# lpc11c14_33.net
KiCad netlist of a schematic drawn in Altium Designer
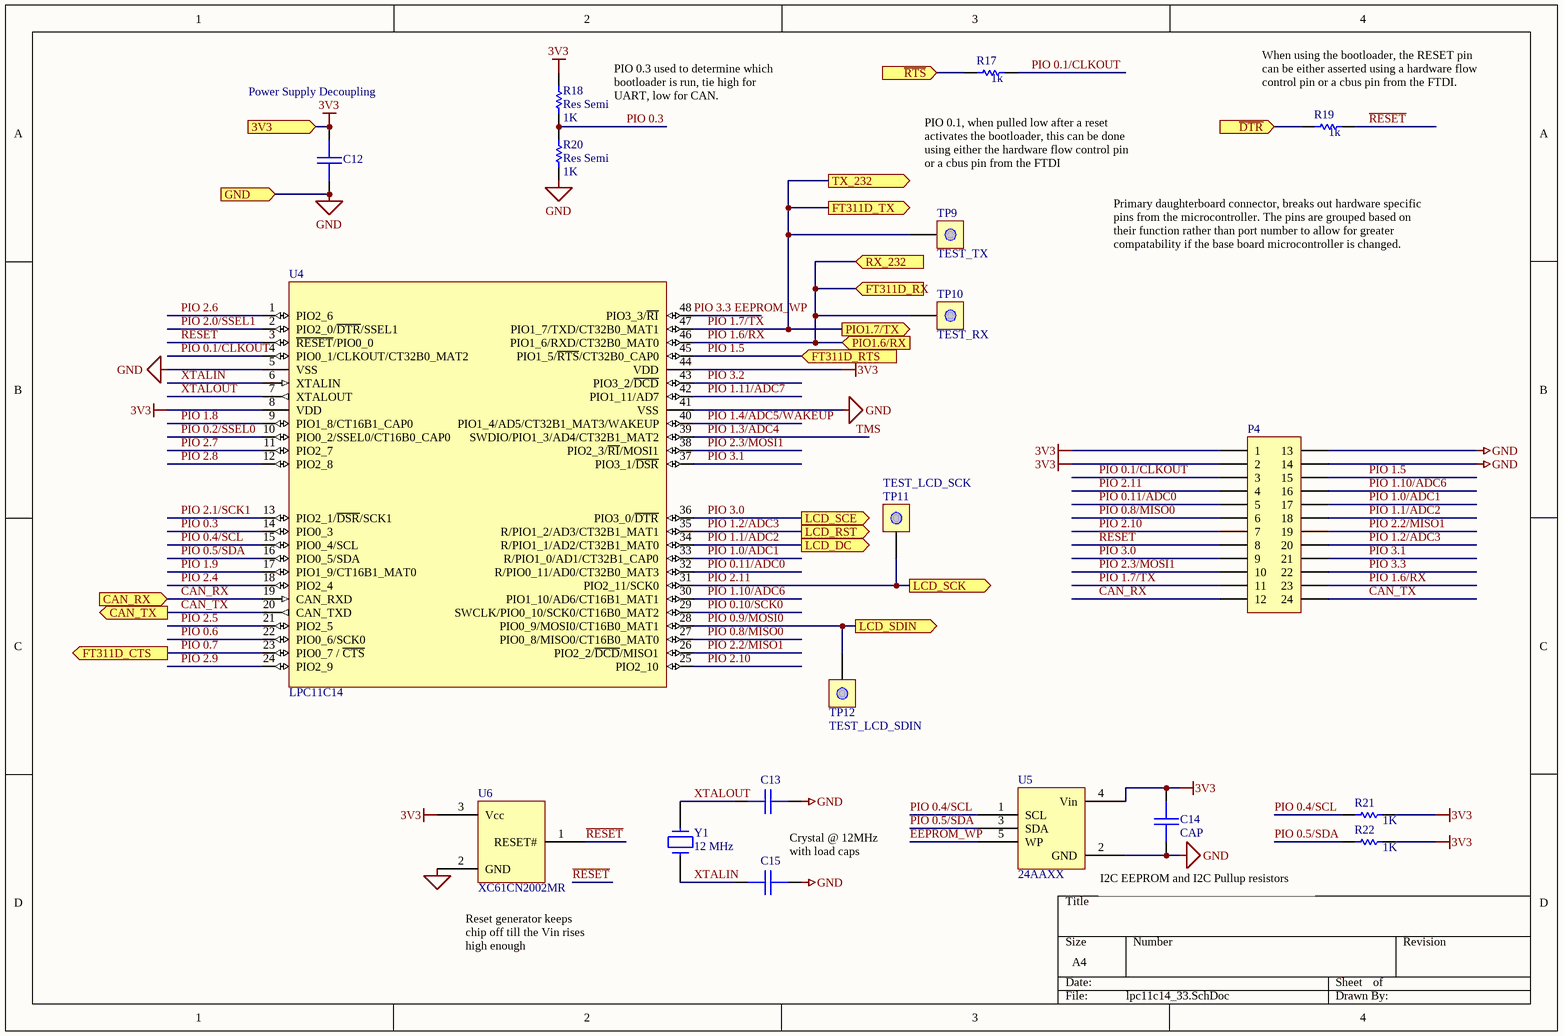
[diagram p0: lpc11c14_33.SchDoc]

(export (version "E")
  (design (tool "Eeschema 10.0.6"))
  (components
    (comp (ref "C12")
      (value "CAP")
      (footprint "0603")
      (description "Capacitor")
      (libsource (lib "RCLDQ") (part "CAP"))
    )
    (comp (ref "C13")
      (value "CAP")
      (footprint "0603")
      (description "Capacitor")
      (libsource (lib "RCLDQ") (part "CAP"))
    )
    (comp (ref "C14")
      (value "CAP")
      (footprint "0603")
      (description "Capacitor")
      (libsource (lib "RCLDQ") (part "CAP"))
    )
    (comp (ref "C15")
      (value "CAP")
      (footprint "0603")
      (description "Capacitor")
      (libsource (lib "RCLDQ") (part "CAP"))
    )
    (comp (ref "P4")
      (value "Header 12X2A")
      (footprint "HDR2X12_CEN")
      (description "Header, 12-Pin, Dual row")
      (fields (field (name "PUBLISHER") "Altium Limited"))
      (libsource (lib "Miscellaneous Connectors") (part "Header 12X2A"))
    )
    (comp (ref "R17")
      (value "1k")
      (footprint "0603")
      (description "Semiconductor Resistor")
      (fields (field (name "Comment") "Res Semi") (field (name "PUBLISHER") "Altium Limited"))
      (libsource (lib "Miscellaneous Devices") (part "Res Semi"))
    )
    (comp (ref "R18")
      (value "Res Semi")
      (footprint "0603")
      (description "Semiconductor Resistor")
      (fields (field (name "ALTIUM_VALUE") "1K") (field (name "PUBLISHER") "Altium Limited"))
      (libsource (lib "Miscellaneous Devices") (part "Res Semi"))
    )
    (comp (ref "R19")
      (value "1k")
      (footprint "0603")
      (description "Semiconductor Resistor")
      (fields (field (name "Comment") "Res Semi") (field (name "PUBLISHER") "Altium Limited"))
      (libsource (lib "Miscellaneous Devices") (part "Res Semi"))
    )
    (comp (ref "R20")
      (value "Res Semi")
      (footprint "0603")
      (description "Semiconductor Resistor")
      (fields (field (name "ALTIUM_VALUE") "1K") (field (name "PUBLISHER") "Altium Limited"))
      (libsource (lib "Miscellaneous Devices") (part "Res Semi"))
    )
    (comp (ref "R21")
      (value "1K")
      (footprint "0603")
      (description "Semiconductor Resistor")
      (fields (field (name "Comment") "Res Semi") (field (name "PUBLISHER") "Altium Limited"))
      (libsource (lib "Miscellaneous Devices") (part "Res Semi"))
    )
    (comp (ref "R22")
      (value "1K")
      (footprint "0603")
      (description "Semiconductor Resistor")
      (fields (field (name "Comment") "Res Semi") (field (name "PUBLISHER") "Altium Limited"))
      (libsource (lib "Miscellaneous Devices") (part "Res Semi"))
    )
    (comp (ref "TP9")
      (value "TEST_TX")
      (footprint "TESTPOINT")
      (description "TEST POINT")
      (libsource (lib "Miscellaneous") (part "TEST"))
    )
    (comp (ref "TP10")
      (value "TEST_RX")
      (footprint "TESTPOINT")
      (description "TEST POINT")
      (libsource (lib "Miscellaneous") (part "TEST"))
    )
    (comp (ref "TP11")
      (value "TEST_LCD_SCK")
      (footprint "TESTPOINT")
      (description "TEST POINT")
      (libsource (lib "") (part "TEST_1"))
    )
    (comp (ref "TP12")
      (value "TEST_LCD_SDIN")
      (footprint "TESTPOINT")
      (description "TEST POINT")
      (libsource (lib "") (part "TEST_2"))
    )
    (comp (ref "U4")
      (value "LPC11C14")
      (footprint "QFP48")
      (description "NXP LPC11C14 Microcontroller")
      (libsource (lib "LPC") (part "LPC11C14_Full"))
    )
    (comp (ref "U5")
      (value "24AAXX")
      (footprint "SOT23-5")
      (description "I2C EEPROM for SOT23-5 package")
      (libsource (lib "MiscellaneousIC") (part "24AAXX"))
    )
    (comp (ref "U6")
      (value "XC61CN2002MR")
      (footprint "SOT23-3")
      (description "SOT23 reset generator")
      (libsource (lib "*") (part "XC61F"))
    )
    (comp (ref "Y1")
      (value "12 MHz")
      (footprint "HC49/4H")
      (description "Crystal")
      (libsource (lib "*") (part "CRYSTAL"))
    )
  )
  (nets
    (net (code "1") (name "/CAN_RX") (class "Default")
      (node (ref "P4") (pin "12") (pinfunction "12_12") (pintype "passive"))
      (node (ref "U4") (pin "19") (pinfunction "CAN_RXD_19") (pintype "input"))
    )
    (net (code "2") (name "/CAN_TX") (class "Default")
      (node (ref "P4") (pin "24") (pinfunction "24_24") (pintype "passive"))
      (node (ref "U4") (pin "20") (pinfunction "CAN_TXD_20") (pintype "output"))
    )
    (net (code "3") (name "/EEPROM_WP") (class "Default")
      (node (ref "P4") (pin "22") (pinfunction "22_22") (pintype "passive"))
      (node (ref "U4") (pin "48") (pinfunction "PIO3_3/~{RI}_48") (pintype "bidirectional"))
      (node (ref "U5") (pin "5") (pinfunction "WP_5") (pintype "passive"))
    )
    (net (code "4") (name "/PIO 0.1{slash}CLKOUT") (class "Default")
      (node (ref "P4") (pin "3") (pinfunction "3_3") (pintype "passive"))
      (node (ref "R17") (pin "2") (pinfunction "2_2") (pintype "passive"))
      (node (ref "U4") (pin "4") (pinfunction "PIO0_1/CLKOUT/CT32B0_MAT2_4") (pintype "bidirectional"))
    )
    (net (code "5") (name "/PIO 0.2{slash}SSEL0") (class "Default")
      (node (ref "U4") (pin "10") (pinfunction "PIO0_2/SSEL0/CT16B0_CAP0_10") (pintype "bidirectional"))
    )
    (net (code "6") (name "/PIO 0.3") (class "Default")
      (node (ref "R18") (pin "1") (pinfunction "1_1") (pintype "passive"))
      (node (ref "R20") (pin "2") (pinfunction "2_2") (pintype "passive"))
      (node (ref "U4") (pin "14") (pinfunction "PIO0_3_14") (pintype "bidirectional"))
    )
    (net (code "7") (name "/PIO 0.4{slash}SCL") (class "Default")
      (node (ref "R21") (pin "1") (pinfunction "1_1") (pintype "passive"))
      (node (ref "U4") (pin "15") (pinfunction "PIO0_4/SCL_15") (pintype "bidirectional"))
      (node (ref "U5") (pin "1") (pinfunction "SCL_1") (pintype "passive"))
    )
    (net (code "8") (name "/PIO 0.5{slash}SDA") (class "Default")
      (node (ref "R22") (pin "1") (pinfunction "1_1") (pintype "passive"))
      (node (ref "U4") (pin "16") (pinfunction "PIO0_5/SDA_16") (pintype "bidirectional"))
      (node (ref "U5") (pin "3") (pinfunction "SDA_3") (pintype "passive"))
    )
    (net (code "9") (name "/PIO 0.6") (class "Default")
      (node (ref "U4") (pin "22") (pinfunction "PIO0_6/SCK0_22") (pintype "bidirectional"))
    )
    (net (code "10") (name "/PIO 0.7") (class "Default")
      (node (ref "U4") (pin "23") (pinfunction "PIO0_7_/_~{CTS}_23") (pintype "bidirectional"))
    )
    (net (code "11") (name "/PIO 0.8{slash}MISO0") (class "Default")
      (node (ref "P4") (pin "6") (pinfunction "6_6") (pintype "passive"))
      (node (ref "U4") (pin "27") (pinfunction "PIO0_8/MISO0/CT16B0_MAT0_27") (pintype "bidirectional"))
    )
    (net (code "12") (name "/PIO 0.9{slash}MOSI0") (class "Default")
      (node (ref "TP12") (pin "0") (pinfunction "TP_0") (pintype "passive"))
      (node (ref "U4") (pin "28") (pinfunction "PIO0_9/MOSI0/CT16B0_MAT1_28") (pintype "bidirectional"))
    )
    (net (code "13") (name "/PIO 0.10{slash}SCK0") (class "Default")
      (node (ref "U4") (pin "29") (pinfunction "SWCLK/PIO0_10/SCK0/CT16B0_MAT2_29") (pintype "bidirectional"))
    )
    (net (code "14") (name "/PIO 0.11{slash}ADC0") (class "Default")
      (node (ref "P4") (pin "5") (pinfunction "5_5") (pintype "passive"))
      (node (ref "U4") (pin "32") (pinfunction "R/PIO0_11/AD0/CT32B0_MAT3_32") (pintype "bidirectional"))
    )
    (net (code "15") (name "/PIO 1.0{slash}ADC1") (class "Default")
      (node (ref "P4") (pin "17") (pinfunction "17_17") (pintype "passive"))
      (node (ref "U4") (pin "33") (pinfunction "R/PIO1_0/AD1/CT32B1_CAP0_33") (pintype "bidirectional"))
    )
    (net (code "16") (name "/PIO 1.1{slash}ADC2") (class "Default")
      (node (ref "P4") (pin "18") (pinfunction "18_18") (pintype "passive"))
      (node (ref "U4") (pin "34") (pinfunction "R/PIO1_1/AD2/CT32B1_MAT0_34") (pintype "bidirectional"))
    )
    (net (code "17") (name "/PIO 1.2{slash}ADC3") (class "Default")
      (node (ref "P4") (pin "20") (pinfunction "20_20") (pintype "passive"))
      (node (ref "U4") (pin "35") (pinfunction "R/PIO1_2/AD3/CT32B1_MAT1_35") (pintype "bidirectional"))
    )
    (net (code "18") (name "/PIO 1.3{slash}ADC4") (class "Default")
      (node (ref "U4") (pin "39") (pinfunction "SWDIO/PIO1_3/AD4/CT32B1_MAT2_39") (pintype "bidirectional"))
    )
    (net (code "19") (name "/PIO 1.4{slash}ADC5{slash}WAKEUP") (class "Default")
      (node (ref "U4") (pin "40") (pinfunction "PIO1_4/AD5/CT32B1_MAT3/WAKEUP_40") (pintype "bidirectional"))
    )
    (net (code "20") (name "/PIO 1.5") (class "Default")
      (node (ref "P4") (pin "15") (pinfunction "15_15") (pintype "passive"))
      (node (ref "U4") (pin "45") (pinfunction "PIO1_5/~{RTS}/CT32B0_CAP0_45") (pintype "bidirectional"))
    )
    (net (code "21") (name "/PIO 1.6{slash}RX") (class "Default")
      (node (ref "P4") (pin "23") (pinfunction "23_23") (pintype "passive"))
      (node (ref "TP10") (pin "0") (pinfunction "TP_0") (pintype "passive"))
      (node (ref "U4") (pin "46") (pinfunction "PIO1_6/RXD/CT32B0_MAT0_46") (pintype "bidirectional"))
    )
    (net (code "22") (name "/PIO 1.7{slash}TX") (class "Default")
      (node (ref "P4") (pin "11") (pinfunction "11_11") (pintype "passive"))
      (node (ref "TP9") (pin "0") (pinfunction "TP_0") (pintype "passive"))
      (node (ref "U4") (pin "47") (pinfunction "PIO1_7/TXD/CT32B0_MAT1_47") (pintype "bidirectional"))
    )
    (net (code "23") (name "/PIO 1.8") (class "Default")
      (node (ref "U4") (pin "9") (pinfunction "PIO1_8/CT16B1_CAP0_9") (pintype "bidirectional"))
    )
    (net (code "24") (name "/PIO 1.9") (class "Default")
      (node (ref "U4") (pin "17") (pinfunction "PIO1_9/CT16B1_MAT0_17") (pintype "bidirectional"))
    )
    (net (code "25") (name "/PIO 1.10{slash}ADC6") (class "Default")
      (node (ref "P4") (pin "16") (pinfunction "16_16") (pintype "passive"))
      (node (ref "U4") (pin "30") (pinfunction "PIO1_10/AD6/CT16B1_MAT1_30") (pintype "bidirectional"))
    )
    (net (code "26") (name "/PIO 1.11{slash}ADC7") (class "Default")
      (node (ref "U4") (pin "42") (pinfunction "PIO1_11/AD7_42") (pintype "bidirectional"))
    )
    (net (code "27") (name "/PIO 2.0{slash}SSEL1") (class "Default")
      (node (ref "U4") (pin "2") (pinfunction "PIO2_0/~{DTR}/SSEL1_2") (pintype "bidirectional"))
    )
    (net (code "28") (name "/PIO 2.1{slash}SCK1") (class "Default")
      (node (ref "U4") (pin "13") (pinfunction "PIO2_1/~{DSR}/SCK1_13") (pintype "bidirectional"))
    )
    (net (code "29") (name "/PIO 2.2{slash}MISO1") (class "Default")
      (node (ref "P4") (pin "19") (pinfunction "19_19") (pintype "passive"))
      (node (ref "U4") (pin "26") (pinfunction "PIO2_2/~{DCD}/MISO1_26") (pintype "bidirectional"))
    )
    (net (code "30") (name "/PIO 2.3{slash}MOSI1") (class "Default")
      (node (ref "P4") (pin "10") (pinfunction "10_10") (pintype "passive"))
      (node (ref "U4") (pin "38") (pinfunction "PIO2_3/~{RI}/MOSI1_38") (pintype "bidirectional"))
    )
    (net (code "31") (name "/PIO 2.4") (class "Default")
      (node (ref "U4") (pin "18") (pinfunction "PIO2_4_18") (pintype "bidirectional"))
    )
    (net (code "32") (name "/PIO 2.5") (class "Default")
      (node (ref "U4") (pin "21") (pinfunction "PIO2_5_21") (pintype "bidirectional"))
    )
    (net (code "33") (name "/PIO 2.6") (class "Default")
      (node (ref "U4") (pin "1") (pinfunction "PIO2_6_1") (pintype "bidirectional"))
    )
    (net (code "34") (name "/PIO 2.7") (class "Default")
      (node (ref "U4") (pin "11") (pinfunction "PIO2_7_11") (pintype "bidirectional"))
    )
    (net (code "35") (name "/PIO 2.8") (class "Default")
      (node (ref "U4") (pin "12") (pinfunction "PIO2_8_12") (pintype "bidirectional"))
    )
    (net (code "36") (name "/PIO 2.9") (class "Default")
      (node (ref "U4") (pin "24") (pinfunction "PIO2_9_24") (pintype "bidirectional"))
    )
    (net (code "37") (name "/PIO 2.10") (class "Default")
      (node (ref "P4") (pin "7") (pinfunction "7_7") (pintype "passive"))
      (node (ref "U4") (pin "25") (pinfunction "PIO2_10_25") (pintype "bidirectional"))
    )
    (net (code "38") (name "/PIO 2.11") (class "Default")
      (node (ref "P4") (pin "4") (pinfunction "4_4") (pintype "passive"))
      (node (ref "TP11") (pin "0") (pinfunction "TP_0") (pintype "passive"))
      (node (ref "U4") (pin "31") (pinfunction "PIO2_11/SCK0_31") (pintype "bidirectional"))
    )
    (net (code "39") (name "/PIO 3.0") (class "Default")
      (node (ref "P4") (pin "9") (pinfunction "9_9") (pintype "passive"))
      (node (ref "U4") (pin "36") (pinfunction "PIO3_0/~{DTR}_36") (pintype "bidirectional"))
    )
    (net (code "40") (name "/PIO 3.1") (class "Default")
      (node (ref "P4") (pin "21") (pinfunction "21_21") (pintype "passive"))
      (node (ref "U4") (pin "37") (pinfunction "PIO3_1/~{DSR}_37") (pintype "bidirectional"))
    )
    (net (code "41") (name "/PIO 3.2") (class "Default")
      (node (ref "U4") (pin "43") (pinfunction "PIO3_2/~{DCD}_43") (pintype "bidirectional"))
    )
    (net (code "42") (name "/XTALIN") (class "Default")
      (node (ref "C15") (pin "1") (pinfunction "1_1") (pintype "passive"))
      (node (ref "U4") (pin "6") (pinfunction "XTALIN_6") (pintype "input"))
      (node (ref "Y1") (pin "1") (pinfunction "1_1") (pintype "passive"))
    )
    (net (code "43") (name "/XTALOUT") (class "Default")
      (node (ref "C13") (pin "1") (pinfunction "1_1") (pintype "passive"))
      (node (ref "U4") (pin "7") (pinfunction "XTALOUT_7") (pintype "output"))
      (node (ref "Y1") (pin "2") (pinfunction "2_2") (pintype "passive"))
    )
    (net (code "44") (name "/~{DTR}") (class "Default")
      (node (ref "R19") (pin "1") (pinfunction "1_1") (pintype "passive"))
    )
    (net (code "45") (name "/~{RESET}") (class "Default")
      (node (ref "P4") (pin "8") (pinfunction "8_8") (pintype "passive"))
      (node (ref "R19") (pin "2") (pinfunction "2_2") (pintype "passive"))
      (node (ref "U4") (pin "3") (pinfunction "~{RESET}/PIO0_0_3") (pintype "bidirectional"))
      (node (ref "U6") (pin "1") (pinfunction "RESET#_1") (pintype "passive"))
    )
    (net (code "46") (name "/~{RTS}") (class "Default")
      (node (ref "R17") (pin "1") (pinfunction "1_1") (pintype "passive"))
    )
    (net (code "47") (name "3V3") (class "Default")
      (node (ref "C12") (pin "1") (pinfunction "1_1") (pintype "passive"))
      (node (ref "C14") (pin "1") (pinfunction "1_1") (pintype "passive"))
      (node (ref "P4") (pin "1") (pinfunction "1_1") (pintype "passive"))
      (node (ref "P4") (pin "2") (pinfunction "2_2") (pintype "passive"))
      (node (ref "R18") (pin "2") (pinfunction "2_2") (pintype "passive"))
      (node (ref "R21") (pin "2") (pinfunction "2_2") (pintype "passive"))
      (node (ref "R22") (pin "2") (pinfunction "2_2") (pintype "passive"))
      (node (ref "U4") (pin "44") (pinfunction "VDD_44") (pintype "power_in"))
      (node (ref "U4") (pin "8") (pinfunction "VDD_8") (pintype "power_in"))
      (node (ref "U5") (pin "4") (pinfunction "Vin_4") (pintype "passive"))
      (node (ref "U6") (pin "3") (pinfunction "Vcc_3") (pintype "passive"))
    )
    (net (code "48") (name "GND") (class "Default")
      (node (ref "C12") (pin "2") (pinfunction "2_2") (pintype "passive"))
      (node (ref "C13") (pin "2") (pinfunction "2_2") (pintype "passive"))
      (node (ref "C14") (pin "2") (pinfunction "2_2") (pintype "passive"))
      (node (ref "C15") (pin "2") (pinfunction "2_2") (pintype "passive"))
      (node (ref "P4") (pin "13") (pinfunction "13_13") (pintype "passive"))
      (node (ref "P4") (pin "14") (pinfunction "14_14") (pintype "passive"))
      (node (ref "R20") (pin "1") (pinfunction "1_1") (pintype "passive"))
      (node (ref "U4") (pin "41") (pinfunction "VSS_41") (pintype "power_in"))
      (node (ref "U4") (pin "5") (pinfunction "VSS_5") (pintype "power_in"))
      (node (ref "U5") (pin "2") (pinfunction "GND_2") (pintype "passive"))
      (node (ref "U6") (pin "2") (pinfunction "GND_2") (pintype "passive"))
    )
  )
)
